# Main.net
KiCad netlist of a schematic drawn in Altium Designer
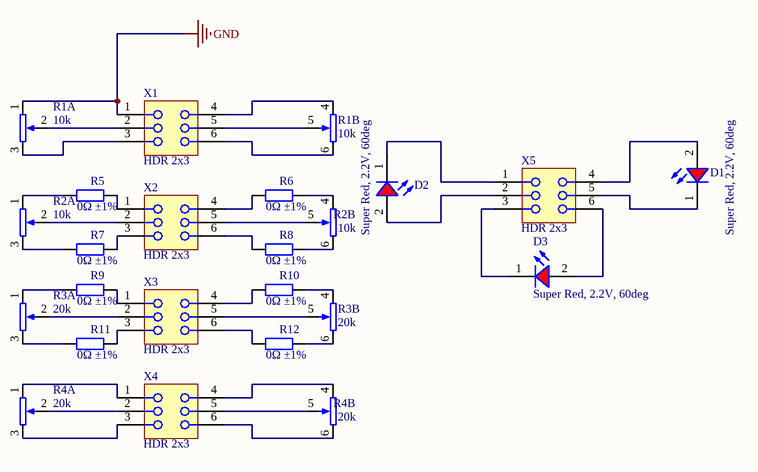
[diagram p0: Main.SchDoc]

(export (version "E")
  (design (tool "Eeschema 10.0.6"))
  (components
    (comp (ref "D1")
      (value "Super Red, 2.2V, 60deg")
      (footprint "WL-TMRC_3mm_10mm_space")
      (description "WL-TMRC THT Mono-color Round Color, size 3mm, Super Red, 2.2V, 60deg")
      (fields
        (field (name "MANUFACTURER PART NUMBER") "151031SS06000")
        (field (name "MANUFACTURER") "Wurth Elektronik")
      )
      (libsource (lib "Diodes") (part "151031SS06000_Spacer_10mm"))
    )
    (comp (ref "D2")
      (value "Super Red, 2.2V, 60deg")
      (footprint "WL-TMRC_3mm_10mm_space")
      (description "WL-TMRC THT Mono-color Round Color, size 3mm, Super Red, 2.2V, 60deg")
      (fields
        (field (name "MANUFACTURER PART NUMBER") "151031SS06000")
        (field (name "MANUFACTURER") "Wurth Elektronik")
      )
      (libsource (lib "Diodes") (part "151031SS06000_Spacer_10mm"))
    )
    (comp (ref "D3")
      (value "Super Red, 2.2V, 60deg")
      (footprint "WL-TMRC_3mm_10mm_space")
      (description "WL-TMRC THT Mono-color Round Color, size 3mm, Super Red, 2.2V, 60deg")
      (fields
        (field (name "MANUFACTURER PART NUMBER") "151031SS06000")
        (field (name "MANUFACTURER") "Wurth Elektronik")
      )
      (libsource (lib "Diodes") (part "151031SS06000_Spacer_10mm"))
    )
    (comp (ref "R1")
      (value "10k")
      (footprint "RK09L2")
      (description "Potentiometers 10K VERTICAL dual, log, audio")
      (fields
        (field (name "MANUFACTURER") "BI Technologies / TT Electronics")
        (field (name "MANUFACTURER PART NUMBER") "P0925N-FC15AR10K")
      )
      (libsource (lib "") (part "POT_10k_log_dual_1"))
    )
    (comp (ref "R2")
      (value "10k")
      (footprint "RK09L2")
      (description "Potentiometers 10K VERTICAL dual, log, audio")
      (fields
        (field (name "MANUFACTURER") "BI Technologies / TT Electronics")
        (field (name "MANUFACTURER PART NUMBER") "P0925N-FC15AR10K")
      )
      (libsource (lib "Resistors") (part "POT_10k_log_dual"))
    )
    (comp (ref "R3")
      (value "20k")
      (footprint "RK09L2")
      (description "Potentiometer 1/20W 20K Ohms 20% 9mm ROTARY POT")
      (fields
        (field (name "MANUFACTURER") "BI Technologies / TT Electronics")
        (field (name "MANUFACTURER PART NUMBER") "P0925N-FC15BR20K")
      )
      (libsource (lib "Resistors") (part "POT_20k_lin_dual"))
    )
    (comp (ref "R4")
      (value "20k")
      (footprint "RK09L2")
      (description "Potentiometer 1/20W 20K Ohms 20% 9mm ROTARY POT")
      (fields
        (field (name "MANUFACTURER") "BI Technologies / TT Electronics")
        (field (name "MANUFACTURER PART NUMBER") "P0925N-FC15BR20K")
      )
      (libsource (lib "") (part "POT_20k_lin_dual_1"))
    )
    (comp (ref "R5")
      (value "0Ω ±1%")
      (footprint "RESC2012X70N")
      (description "Chip resistor")
      (fields (field (name "TOLERANCE") "1%") (field (name "MANUFACTURER PART NUMBER") "CRCW08050000Z0EAC"))
      (libsource (lib "Resistors") (part "0805 0R (0R0) 1%"))
    )
    (comp (ref "R6")
      (value "0Ω ±1%")
      (footprint "RESC2012X70N")
      (description "Chip resistor")
      (fields (field (name "TOLERANCE") "1%") (field (name "MANUFACTURER PART NUMBER") "CRCW08050000Z0EAC"))
      (libsource (lib "Resistors") (part "0805 0R (0R0) 1%"))
    )
    (comp (ref "R7")
      (value "0Ω ±1%")
      (footprint "RESC2012X70N")
      (description "Chip resistor")
      (fields (field (name "TOLERANCE") "1%") (field (name "MANUFACTURER PART NUMBER") "CRCW08050000Z0EAC"))
      (libsource (lib "Resistors") (part "0805 0R (0R0) 1%"))
    )
    (comp (ref "R8")
      (value "0Ω ±1%")
      (footprint "RESC2012X70N")
      (description "Chip resistor")
      (fields (field (name "TOLERANCE") "1%") (field (name "MANUFACTURER PART NUMBER") "CRCW08050000Z0EAC"))
      (libsource (lib "Resistors") (part "0805 0R (0R0) 1%"))
    )
    (comp (ref "R9")
      (value "0Ω ±1%")
      (footprint "RESC2012X70N")
      (description "Chip resistor")
      (fields (field (name "TOLERANCE") "1%") (field (name "MANUFACTURER PART NUMBER") "CRCW08050000Z0EAC"))
      (libsource (lib "Resistors") (part "0805 0R (0R0) 1%"))
    )
    (comp (ref "R10")
      (value "0Ω ±1%")
      (footprint "RESC2012X70N")
      (description "Chip resistor")
      (fields (field (name "TOLERANCE") "1%") (field (name "MANUFACTURER PART NUMBER") "CRCW08050000Z0EAC"))
      (libsource (lib "Resistors") (part "0805 0R (0R0) 1%"))
    )
    (comp (ref "R11")
      (value "0Ω ±1%")
      (footprint "RESC2012X70N")
      (description "Chip resistor")
      (fields (field (name "TOLERANCE") "1%") (field (name "MANUFACTURER PART NUMBER") "CRCW08050000Z0EAC"))
      (libsource (lib "Resistors") (part "0805 0R (0R0) 1%"))
    )
    (comp (ref "R12")
      (value "0Ω ±1%")
      (footprint "RESC2012X70N")
      (description "Chip resistor")
      (fields (field (name "TOLERANCE") "1%") (field (name "MANUFACTURER PART NUMBER") "CRCW08050000Z0EAC"))
      (libsource (lib "Resistors") (part "0805 0R (0R0) 1%"))
    )
    (comp (ref "X1")
      (value "HDR 2x3")
      (footprint "61300621121-poti")
      (fields (field (name "MANUFACTURER") "WE") (field (name "MANUFACTURER PART NUMBER") "613004216921"))
      (libsource (lib "Connectors") (part "CON_HEADER_2x3_Poti"))
    )
    (comp (ref "X2")
      (value "HDR 2x3")
      (footprint "61300621121-poti")
      (fields (field (name "MANUFACTURER") "WE") (field (name "MANUFACTURER PART NUMBER") "613004216921"))
      (libsource (lib "Connectors") (part "CON_HEADER_2x3_Poti"))
    )
    (comp (ref "X3")
      (value "HDR 2x3")
      (footprint "61300621121-poti")
      (fields (field (name "MANUFACTURER") "WE") (field (name "MANUFACTURER PART NUMBER") "613004216921"))
      (libsource (lib "Connectors") (part "CON_HEADER_2x3_Poti"))
    )
    (comp (ref "X4")
      (value "HDR 2x3")
      (footprint "61300621121-poti")
      (fields (field (name "MANUFACTURER") "WE") (field (name "MANUFACTURER PART NUMBER") "613004216921"))
      (libsource (lib "Connectors") (part "CON_HEADER_2x3_Poti"))
    )
    (comp (ref "X5")
      (value "HDR 2x3")
      (footprint "61300621121-poti")
      (fields (field (name "MANUFACTURER") "WE") (field (name "MANUFACTURER PART NUMBER") "613004216921"))
      (libsource (lib "Connectors") (part "CON_HEADER_2x3_Poti"))
    )
  )
  (nets
    (net (code "1") (name "GND") (class "Default")
      (node (ref "R1") (pin "1") (pinfunction "1_1") (pintype "passive"))
      (node (ref "X1") (pin "1") (pinfunction "1_1") (pintype "passive"))
    )
    (net (code "2") (name "Net-(D1-A)") (class "Default")
      (node (ref "D1") (pin "2") (pinfunction "A_2") (pintype "passive"))
      (node (ref "X5") (pin "4") (pinfunction "4_4") (pintype "passive"))
    )
    (net (code "3") (name "Net-(D1-K)") (class "Default")
      (node (ref "D1") (pin "1") (pinfunction "K_1") (pintype "passive"))
      (node (ref "X5") (pin "5") (pinfunction "5_5") (pintype "passive"))
    )
    (net (code "4") (name "Net-(D2-A)") (class "Default")
      (node (ref "D2") (pin "2") (pinfunction "A_2") (pintype "passive"))
      (node (ref "X5") (pin "2") (pinfunction "2_2") (pintype "passive"))
    )
    (net (code "5") (name "Net-(D2-K)") (class "Default")
      (node (ref "D2") (pin "1") (pinfunction "K_1") (pintype "passive"))
      (node (ref "X5") (pin "1") (pinfunction "1_1") (pintype "passive"))
    )
    (net (code "6") (name "Net-(D3-A)") (class "Default")
      (node (ref "D3") (pin "2") (pinfunction "A_2") (pintype "passive"))
      (node (ref "X5") (pin "6") (pinfunction "6_6") (pintype "passive"))
    )
    (net (code "7") (name "Net-(D3-K)") (class "Default")
      (node (ref "D3") (pin "1") (pinfunction "K_1") (pintype "passive"))
      (node (ref "X5") (pin "3") (pinfunction "3_3") (pintype "passive"))
    )
    (net (code "8") (name "Net-(R1-Pad2)") (class "Default")
      (node (ref "R1") (pin "2") (pinfunction "2_2") (pintype "passive"))
      (node (ref "X1") (pin "2") (pinfunction "2_2") (pintype "passive"))
    )
    (net (code "9") (name "Net-(R1-Pad3)") (class "Default")
      (node (ref "R1") (pin "3") (pinfunction "3_3") (pintype "passive"))
      (node (ref "X1") (pin "3") (pinfunction "3_3") (pintype "passive"))
    )
    (net (code "10") (name "Net-(R1-Pad4)") (class "Default")
      (node (ref "R1") (pin "4") (pinfunction "4_4") (pintype "passive"))
      (node (ref "X1") (pin "4") (pinfunction "4_4") (pintype "passive"))
    )
    (net (code "11") (name "Net-(R1-Pad5)") (class "Default")
      (node (ref "R1") (pin "5") (pinfunction "5_5") (pintype "passive"))
      (node (ref "X1") (pin "5") (pinfunction "5_5") (pintype "passive"))
    )
    (net (code "12") (name "Net-(R1-Pad6)") (class "Default")
      (node (ref "R1") (pin "6") (pinfunction "6_6") (pintype "passive"))
      (node (ref "X1") (pin "6") (pinfunction "6_6") (pintype "passive"))
    )
    (net (code "13") (name "Net-(R2-Pad1)") (class "Default")
      (node (ref "R2") (pin "1") (pinfunction "1_1") (pintype "passive"))
      (node (ref "R5") (pin "1") (pinfunction "1_1") (pintype "passive"))
    )
    (net (code "14") (name "Net-(R2-Pad2)") (class "Default")
      (node (ref "R2") (pin "2") (pinfunction "2_2") (pintype "passive"))
      (node (ref "X2") (pin "2") (pinfunction "2_2") (pintype "passive"))
    )
    (net (code "15") (name "Net-(R2-Pad3)") (class "Default")
      (node (ref "R2") (pin "3") (pinfunction "3_3") (pintype "passive"))
      (node (ref "R7") (pin "1") (pinfunction "1_1") (pintype "passive"))
    )
    (net (code "16") (name "Net-(R2-Pad4)") (class "Default")
      (node (ref "R2") (pin "4") (pinfunction "4_4") (pintype "passive"))
      (node (ref "R6") (pin "2") (pinfunction "2_2") (pintype "passive"))
    )
    (net (code "17") (name "Net-(R2-Pad5)") (class "Default")
      (node (ref "R2") (pin "5") (pinfunction "5_5") (pintype "passive"))
      (node (ref "X2") (pin "5") (pinfunction "5_5") (pintype "passive"))
    )
    (net (code "18") (name "Net-(R2-Pad6)") (class "Default")
      (node (ref "R2") (pin "6") (pinfunction "6_6") (pintype "passive"))
      (node (ref "R8") (pin "2") (pinfunction "2_2") (pintype "passive"))
    )
    (net (code "19") (name "Net-(R3-Pad1)") (class "Default")
      (node (ref "R3") (pin "1") (pinfunction "1_1") (pintype "passive"))
      (node (ref "R9") (pin "1") (pinfunction "1_1") (pintype "passive"))
    )
    (net (code "20") (name "Net-(R3-Pad2)") (class "Default")
      (node (ref "R3") (pin "2") (pinfunction "2_2") (pintype "passive"))
      (node (ref "X3") (pin "2") (pinfunction "2_2") (pintype "passive"))
    )
    (net (code "21") (name "Net-(R3-Pad5)") (class "Default")
      (node (ref "R3") (pin "5") (pinfunction "5_5") (pintype "passive"))
      (node (ref "X3") (pin "5") (pinfunction "5_5") (pintype "passive"))
    )
    (net (code "22") (name "Net-(R4-Pad1)") (class "Default")
      (node (ref "R4") (pin "1") (pinfunction "1_1") (pintype "passive"))
      (node (ref "X4") (pin "1") (pinfunction "1_1") (pintype "passive"))
    )
    (net (code "23") (name "Net-(R4-Pad2)") (class "Default")
      (node (ref "R4") (pin "2") (pinfunction "2_2") (pintype "passive"))
      (node (ref "X4") (pin "2") (pinfunction "2_2") (pintype "passive"))
    )
    (net (code "24") (name "Net-(R4-Pad3)") (class "Default")
      (node (ref "R4") (pin "3") (pinfunction "3_3") (pintype "passive"))
      (node (ref "X4") (pin "3") (pinfunction "3_3") (pintype "passive"))
    )
    (net (code "25") (name "Net-(R4-Pad4)") (class "Default")
      (node (ref "R4") (pin "4") (pinfunction "4_4") (pintype "passive"))
      (node (ref "X4") (pin "4") (pinfunction "4_4") (pintype "passive"))
    )
    (net (code "26") (name "Net-(R4-Pad5)") (class "Default")
      (node (ref "R4") (pin "5") (pinfunction "5_5") (pintype "passive"))
      (node (ref "X4") (pin "5") (pinfunction "5_5") (pintype "passive"))
    )
    (net (code "27") (name "Net-(R4-Pad6)") (class "Default")
      (node (ref "R4") (pin "6") (pinfunction "6_6") (pintype "passive"))
      (node (ref "X4") (pin "6") (pinfunction "6_6") (pintype "passive"))
    )
    (net (code "28") (name "Net-(R5-Pad2)") (class "Default")
      (node (ref "R5") (pin "2") (pinfunction "2_2") (pintype "passive"))
      (node (ref "X2") (pin "1") (pinfunction "1_1") (pintype "passive"))
    )
    (net (code "29") (name "Net-(R6-Pad1)") (class "Default")
      (node (ref "R6") (pin "1") (pinfunction "1_1") (pintype "passive"))
      (node (ref "X2") (pin "4") (pinfunction "4_4") (pintype "passive"))
    )
    (net (code "30") (name "Net-(R7-Pad2)") (class "Default")
      (node (ref "R7") (pin "2") (pinfunction "2_2") (pintype "passive"))
      (node (ref "X2") (pin "3") (pinfunction "3_3") (pintype "passive"))
    )
    (net (code "31") (name "Net-(R8-Pad1)") (class "Default")
      (node (ref "R8") (pin "1") (pinfunction "1_1") (pintype "passive"))
      (node (ref "X2") (pin "6") (pinfunction "6_6") (pintype "passive"))
    )
    (net (code "32") (name "Net-(R9-Pad2)") (class "Default")
      (node (ref "R9") (pin "2") (pinfunction "2_2") (pintype "passive"))
      (node (ref "X3") (pin "1") (pinfunction "1_1") (pintype "passive"))
    )
    (net (code "33") (name "Net-(R10-Pad1)") (class "Default")
      (node (ref "R10") (pin "1") (pinfunction "1_1") (pintype "passive"))
      (node (ref "X3") (pin "4") (pinfunction "4_4") (pintype "passive"))
    )
    (net (code "34") (name "Net-(R10-Pad2)") (class "Default")
      (node (ref "R10") (pin "2") (pinfunction "2_2") (pintype "passive"))
      (node (ref "R3") (pin "4") (pinfunction "4_4") (pintype "passive"))
    )
    (net (code "35") (name "Net-(R11-Pad1)") (class "Default")
      (node (ref "R11") (pin "1") (pinfunction "1_1") (pintype "passive"))
      (node (ref "R3") (pin "3") (pinfunction "3_3") (pintype "passive"))
    )
    (net (code "36") (name "Net-(R11-Pad2)") (class "Default")
      (node (ref "R11") (pin "2") (pinfunction "2_2") (pintype "passive"))
      (node (ref "X3") (pin "3") (pinfunction "3_3") (pintype "passive"))
    )
    (net (code "37") (name "Net-(R12-Pad1)") (class "Default")
      (node (ref "R12") (pin "1") (pinfunction "1_1") (pintype "passive"))
      (node (ref "X3") (pin "6") (pinfunction "6_6") (pintype "passive"))
    )
    (net (code "38") (name "Net-(R12-Pad2)") (class "Default")
      (node (ref "R12") (pin "2") (pinfunction "2_2") (pintype "passive"))
      (node (ref "R3") (pin "6") (pinfunction "6_6") (pintype "passive"))
    )
  )
)
